# Buck.net
KiCad netlist of a schematic drawn in Altium Designer
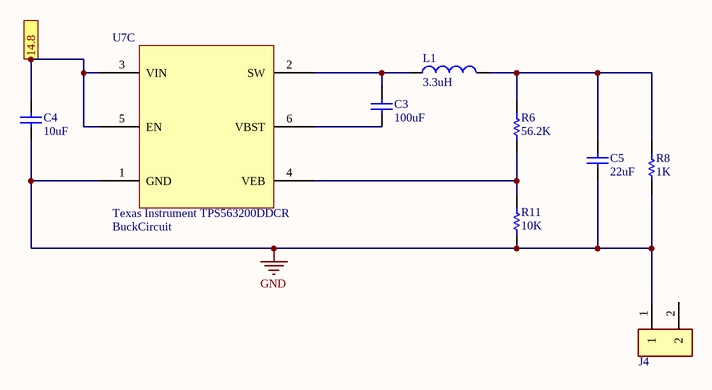
[diagram p0: Buck.SchDoc]

(export (version "E")
  (design (tool "Eeschema 10.0.6"))
  (components
    (comp (ref "C3")
      (value "100uF")
      (footprint "0805")
      (description "Capacitor")
      (libsource (lib "Simulation Generic Components") (part "Capacitor"))
    )
    (comp (ref "C4")
      (value "10uF")
      (footprint "0805")
      (description "Capacitor")
      (libsource (lib "Simulation Generic Components") (part "Capacitor"))
    )
    (comp (ref "C5")
      (value "22uF")
      (footprint "0805")
      (description "Capacitor")
      (libsource (lib "Simulation Generic Components") (part "Capacitor"))
    )
    (comp (ref "J4")
      (value "1935161")
      (footprint "PHOENIX_1935161")
      (description "Conn Terminal Blocks 2 POS 5mm Solder ST Thru-Hole 16A")
      (fields (field (name "MF") "{'manufacturer': u'Phoenix Contact'}"))
      (libsource (lib "1935161") (part "1935161"))
    )
    (comp (ref "L1")
      (value "3.3uH")
      (footprint "0805")
      (description "Inductor")
      (libsource (lib "Simulation Generic Components") (part "Inductor"))
    )
    (comp (ref "R6")
      (value "56.2K")
      (footprint "0805")
      (description "Resistor")
      (libsource (lib "Simulation Generic Components") (part "Resistor"))
    )
    (comp (ref "R8")
      (value "1K")
      (footprint "0805")
      (description "Resistor")
      (libsource (lib "Simulation Generic Components") (part "Resistor"))
    )
    (comp (ref "R11")
      (value "10K")
      (footprint "0805")
      (description "Resistor")
      (libsource (lib "Simulation Generic Components") (part "Resistor"))
    )
    (comp (ref "U7")
      (value "BuckCircuit")
      (footprint "SOT95P280X110-6N")
      (libsource (lib "Schlib1") (part "BuckCircuit"))
    )
  )
  (nets
    (net (code "1") (name "/14.8") (class "Default")
      (node (ref "C4") (pin "2") (pinfunction "2_2") (pintype "passive"))
      (node (ref "U7") (pin "3") (pinfunction "VIN_3") (pintype "passive"))
      (node (ref "U7") (pin "5") (pinfunction "EN_5") (pintype "passive"))
    )
    (net (code "2") (name "GND") (class "Default")
      (node (ref "C4") (pin "1") (pinfunction "1_1") (pintype "passive"))
      (node (ref "C5") (pin "1") (pinfunction "1_1") (pintype "passive"))
      (node (ref "J4") (pin "1") (pinfunction "1_1") (pintype "passive"))
      (node (ref "R11") (pin "1") (pinfunction "1_1") (pintype "passive"))
      (node (ref "R8") (pin "1") (pinfunction "1_1") (pintype "passive"))
      (node (ref "U7") (pin "1") (pinfunction "GND_1") (pintype "passive"))
    )
    (net (code "3") (name "Net-(C5-Pad2)") (class "Default")
      (node (ref "C5") (pin "2") (pinfunction "2_2") (pintype "passive"))
      (node (ref "L1") (pin "2") (pinfunction "2_2") (pintype "passive"))
      (node (ref "R6") (pin "2") (pinfunction "2_2") (pintype "passive"))
      (node (ref "R8") (pin "2") (pinfunction "2_2") (pintype "passive"))
    )
    (net (code "4") (name "Net-(U7C-SW)") (class "Default")
      (node (ref "C3") (pin "2") (pinfunction "2_2") (pintype "passive"))
      (node (ref "L1") (pin "1") (pinfunction "1_1") (pintype "passive"))
      (node (ref "U7") (pin "2") (pinfunction "SW_2") (pintype "passive"))
    )
    (net (code "5") (name "Net-(U7C-VBST)") (class "Default")
      (node (ref "C3") (pin "1") (pinfunction "1_1") (pintype "passive"))
      (node (ref "U7") (pin "6") (pinfunction "VBST_6") (pintype "passive"))
    )
    (net (code "6") (name "Net-(U7C-VEB)") (class "Default")
      (node (ref "R11") (pin "2") (pinfunction "2_2") (pintype "passive"))
      (node (ref "R6") (pin "1") (pinfunction "1_1") (pintype "passive"))
      (node (ref "U7") (pin "4") (pinfunction "VEB_4") (pintype "passive"))
    )
    (net (code "7") (name "unconnected-(J4-Pad2)") (class "Default")
      (node (ref "J4") (pin "2") (pinfunction "2_2") (pintype "passive"))
    )
  )
)
